# 07_MCU.net
KiCad netlist of a schematic drawn in Altium Designer
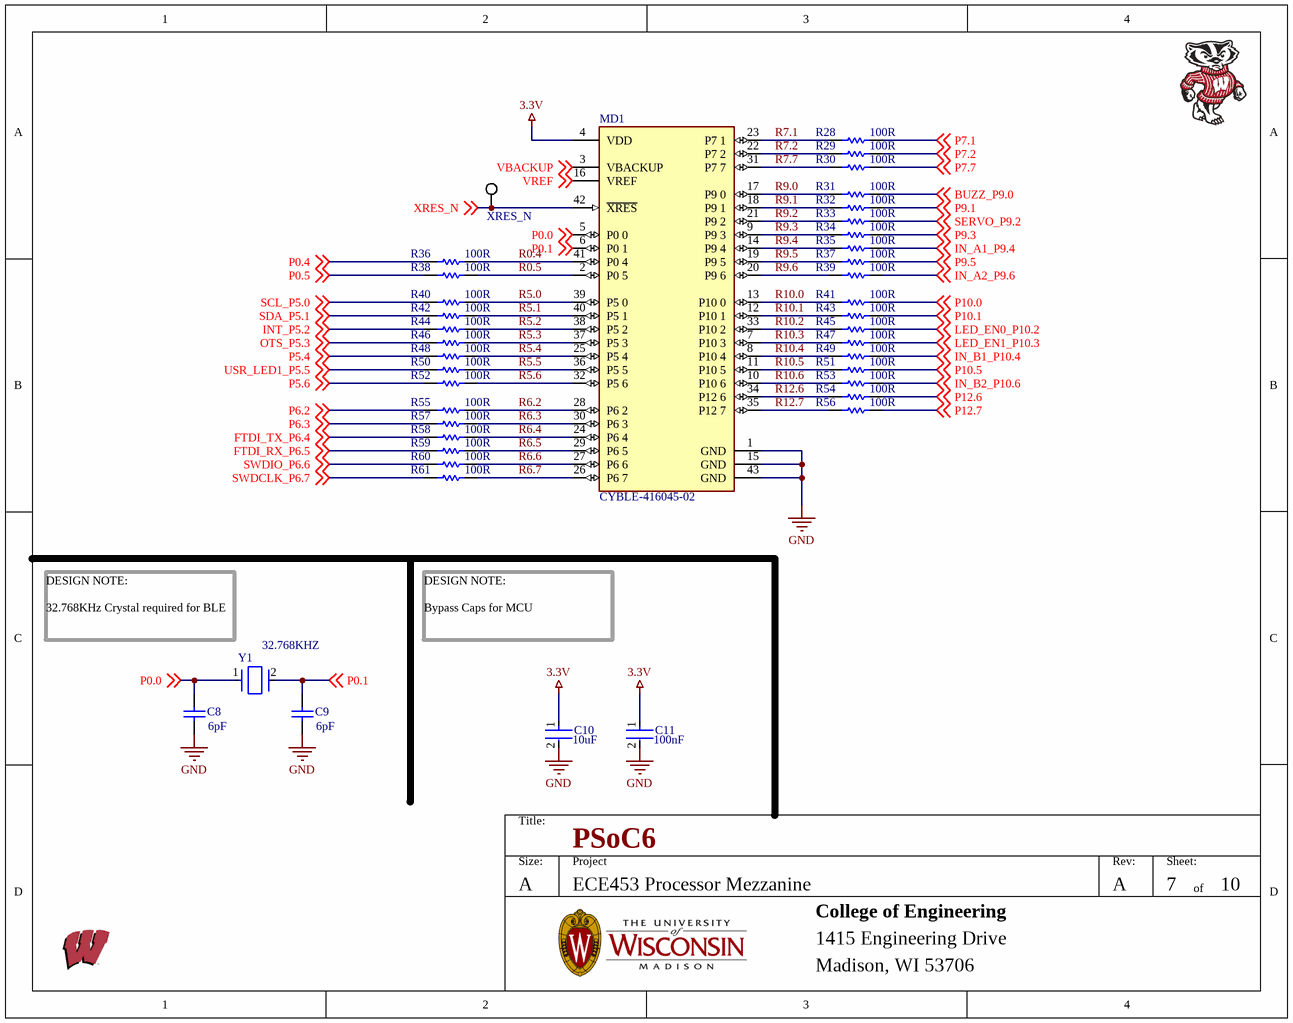
[diagram p0: 07_MCU.SchDoc]

(export (version "E")
  (design (tool "Eeschema 10.0.6"))
  (components
    (comp (ref "C8")
      (value "6pF")
      (footprint "CAPC2013X94X50LL20T25")
      (fields
        (field (name "MANUFACTURER") "KEMET")
        (field (name "MANUFACTURER PART NUMBER") "CBR08C609C5GAC")
        (field (name "Comment") "08055A6R0CAT2A")
      )
      (libsource (lib "Altium Content Vault") (part "CAP"))
    )
    (comp (ref "C9")
      (value "6pF")
      (footprint "CAPC2013X94X50LL20T25")
      (fields
        (field (name "MANUFACTURER") "KEMET")
        (field (name "MANUFACTURER PART NUMBER") "CBR08C609C5GAC")
        (field (name "Comment") "08055A6R0CAT2A")
      )
      (libsource (lib "Altium Content Vault") (part "CAP"))
    )
    (comp (ref "C10")
      (value "10uF")
      (footprint "FP-C0805C-DG-MFG")
      (description "CAP CER 10UF 10V X5R 0805")
      (fields
        (field (name "MANUFACTURER") "KEMET")
        (field (name "MANUFACTURER PART NUMBER") "C0805C106K8PACTU")
      )
      (libsource (lib "Altium Content Vault") (part "11868f565c42a9108669ba33697ecf6"))
    )
    (comp (ref "C11")
      (value "100nF")
      (footprint "FP-C0805C-DN-MFG")
      (description "CAP CER 0.1UF 50V X7R 0805")
      (fields
        (field (name "MANUFACTURER") "KEMET")
        (field (name "MANUFACTURER PART NUMBER") "C0805C104K5RACTU")
      )
      (libsource (lib "Altium Content Vault") (part "b4654b650e69147ec39a6b967a45e02"))
    )
    (comp (ref "MD1")
      (value "CYBLE-416045-02")
      (footprint "FP-CYBLE-416045-02-MFG")
      (description "RF TXRX MOD BLUETOOTH TRACE ANT")
      (fields
        (field (name "OCTOPART") "https://octopart.com/cyble-416045-02-cypress+semiconductor-96386825")
        (field (name "MANUFACTURER") "Cypress Semiconductor")
      )
      (libsource (lib "Altium Content Vault") (part "10a29a4e77099fbb6f911efb04878b1"))
    )
    (comp (ref "R28")
      (value "100R")
      (footprint "RESC2013X60X40ML20T25")
      (fields
        (field (name "MANUFACTURER") "Yageo")
        (field (name "MANUFACTURER PART NUMBER") "RC0805FR-07100RL")
        (field (name "TOLERANCE") "1%")
      )
      (libsource (lib "Altium Content Vault") (part "RES"))
    )
    (comp (ref "R29")
      (value "100R")
      (footprint "RESC2013X60X40ML20T25")
      (fields
        (field (name "MANUFACTURER") "Yageo")
        (field (name "MANUFACTURER PART NUMBER") "RC0805FR-07100RL")
        (field (name "TOLERANCE") "1%")
      )
      (libsource (lib "Altium Content Vault") (part "RES"))
    )
    (comp (ref "R30")
      (value "100R")
      (footprint "RESC2013X60X40ML20T25")
      (fields
        (field (name "MANUFACTURER") "Yageo")
        (field (name "MANUFACTURER PART NUMBER") "RC0805FR-07100RL")
        (field (name "TOLERANCE") "1%")
      )
      (libsource (lib "Altium Content Vault") (part "RES"))
    )
    (comp (ref "R31")
      (value "100R")
      (footprint "RESC2013X60X40ML20T25")
      (fields
        (field (name "MANUFACTURER") "Yageo")
        (field (name "MANUFACTURER PART NUMBER") "RC0805FR-07100RL")
        (field (name "TOLERANCE") "1%")
      )
      (libsource (lib "Altium Content Vault") (part "RES"))
    )
    (comp (ref "R32")
      (value "100R")
      (footprint "RESC2013X60X40ML20T25")
      (fields
        (field (name "MANUFACTURER") "Yageo")
        (field (name "MANUFACTURER PART NUMBER") "RC0805FR-07100RL")
        (field (name "TOLERANCE") "1%")
      )
      (libsource (lib "Altium Content Vault") (part "RES"))
    )
    (comp (ref "R33")
      (value "100R")
      (footprint "RESC2013X60X40ML20T25")
      (fields
        (field (name "MANUFACTURER") "Yageo")
        (field (name "MANUFACTURER PART NUMBER") "RC0805FR-07100RL")
        (field (name "TOLERANCE") "1%")
      )
      (libsource (lib "Altium Content Vault") (part "RES"))
    )
    (comp (ref "R34")
      (value "100R")
      (footprint "RESC2013X60X40ML20T25")
      (fields
        (field (name "MANUFACTURER") "Yageo")
        (field (name "MANUFACTURER PART NUMBER") "RC0805FR-07100RL")
        (field (name "TOLERANCE") "1%")
      )
      (libsource (lib "Altium Content Vault") (part "RES"))
    )
    (comp (ref "R35")
      (value "100R")
      (footprint "RESC2013X60X40ML20T25")
      (fields
        (field (name "MANUFACTURER") "Yageo")
        (field (name "MANUFACTURER PART NUMBER") "RC0805FR-07100RL")
        (field (name "TOLERANCE") "1%")
      )
      (libsource (lib "Altium Content Vault") (part "RES"))
    )
    (comp (ref "R36")
      (value "100R")
      (footprint "RESC2013X60X40ML20T25")
      (fields
        (field (name "MANUFACTURER") "Yageo")
        (field (name "MANUFACTURER PART NUMBER") "RC0805FR-07100RL")
        (field (name "TOLERANCE") "1%")
      )
      (libsource (lib "Altium Content Vault") (part "RES"))
    )
    (comp (ref "R37")
      (value "100R")
      (footprint "RESC2013X60X40ML20T25")
      (fields
        (field (name "MANUFACTURER") "Yageo")
        (field (name "MANUFACTURER PART NUMBER") "RC0805FR-07100RL")
        (field (name "TOLERANCE") "1%")
      )
      (libsource (lib "Altium Content Vault") (part "RES"))
    )
    (comp (ref "R38")
      (value "100R")
      (footprint "RESC2013X60X40ML20T25")
      (fields
        (field (name "MANUFACTURER") "Yageo")
        (field (name "MANUFACTURER PART NUMBER") "RC0805FR-07100RL")
        (field (name "TOLERANCE") "1%")
      )
      (libsource (lib "Altium Content Vault") (part "RES"))
    )
    (comp (ref "R39")
      (value "100R")
      (footprint "RESC2013X60X40ML20T25")
      (fields
        (field (name "MANUFACTURER") "Yageo")
        (field (name "MANUFACTURER PART NUMBER") "RC0805FR-07100RL")
        (field (name "TOLERANCE") "1%")
      )
      (libsource (lib "Altium Content Vault") (part "RES"))
    )
    (comp (ref "R40")
      (value "100R")
      (footprint "RESC2013X60X40ML20T25")
      (fields
        (field (name "MANUFACTURER") "Yageo")
        (field (name "MANUFACTURER PART NUMBER") "RC0805FR-07100RL")
        (field (name "TOLERANCE") "1%")
      )
      (libsource (lib "Altium Content Vault") (part "RES"))
    )
    (comp (ref "R41")
      (value "100R")
      (footprint "RESC2013X60X40ML20T25")
      (fields
        (field (name "MANUFACTURER") "Yageo")
        (field (name "MANUFACTURER PART NUMBER") "RC0805FR-07100RL")
        (field (name "TOLERANCE") "1%")
      )
      (libsource (lib "Altium Content Vault") (part "RES"))
    )
    (comp (ref "R42")
      (value "100R")
      (footprint "RESC2013X60X40ML20T25")
      (fields
        (field (name "MANUFACTURER") "Yageo")
        (field (name "MANUFACTURER PART NUMBER") "RC0805FR-07100RL")
        (field (name "TOLERANCE") "1%")
      )
      (libsource (lib "Altium Content Vault") (part "RES"))
    )
    (comp (ref "R43")
      (value "100R")
      (footprint "RESC2013X60X40ML20T25")
      (fields
        (field (name "MANUFACTURER") "Yageo")
        (field (name "MANUFACTURER PART NUMBER") "RC0805FR-07100RL")
        (field (name "TOLERANCE") "1%")
      )
      (libsource (lib "Altium Content Vault") (part "RES"))
    )
    (comp (ref "R44")
      (value "100R")
      (footprint "RESC2013X60X40ML20T25")
      (fields
        (field (name "MANUFACTURER") "Yageo")
        (field (name "MANUFACTURER PART NUMBER") "RC0805FR-07100RL")
        (field (name "TOLERANCE") "1%")
      )
      (libsource (lib "Altium Content Vault") (part "RES"))
    )
    (comp (ref "R45")
      (value "100R")
      (footprint "RESC2013X60X40ML20T25")
      (fields
        (field (name "MANUFACTURER") "Yageo")
        (field (name "MANUFACTURER PART NUMBER") "RC0805FR-07100RL")
        (field (name "TOLERANCE") "1%")
      )
      (libsource (lib "Altium Content Vault") (part "RES"))
    )
    (comp (ref "R46")
      (value "100R")
      (footprint "RESC2013X60X40ML20T25")
      (fields
        (field (name "MANUFACTURER") "Yageo")
        (field (name "MANUFACTURER PART NUMBER") "RC0805FR-07100RL")
        (field (name "TOLERANCE") "1%")
      )
      (libsource (lib "Altium Content Vault") (part "RES"))
    )
    (comp (ref "R47")
      (value "100R")
      (footprint "RESC2013X60X40ML20T25")
      (fields
        (field (name "MANUFACTURER") "Yageo")
        (field (name "MANUFACTURER PART NUMBER") "RC0805FR-07100RL")
        (field (name "TOLERANCE") "1%")
      )
      (libsource (lib "Altium Content Vault") (part "RES"))
    )
    (comp (ref "R48")
      (value "100R")
      (footprint "RESC2013X60X40ML20T25")
      (fields
        (field (name "MANUFACTURER") "Yageo")
        (field (name "MANUFACTURER PART NUMBER") "RC0805FR-07100RL")
        (field (name "TOLERANCE") "1%")
      )
      (libsource (lib "Altium Content Vault") (part "RES"))
    )
    (comp (ref "R49")
      (value "100R")
      (footprint "RESC2013X60X40ML20T25")
      (fields
        (field (name "MANUFACTURER") "Yageo")
        (field (name "MANUFACTURER PART NUMBER") "RC0805FR-07100RL")
        (field (name "TOLERANCE") "1%")
      )
      (libsource (lib "Altium Content Vault") (part "RES"))
    )
    (comp (ref "R50")
      (value "100R")
      (footprint "RESC2013X60X40ML20T25")
      (fields
        (field (name "MANUFACTURER") "Yageo")
        (field (name "MANUFACTURER PART NUMBER") "RC0805FR-07100RL")
        (field (name "TOLERANCE") "1%")
      )
      (libsource (lib "Altium Content Vault") (part "RES"))
    )
    (comp (ref "R51")
      (value "100R")
      (footprint "RESC2013X60X40ML20T25")
      (fields
        (field (name "MANUFACTURER") "Yageo")
        (field (name "MANUFACTURER PART NUMBER") "RC0805FR-07100RL")
        (field (name "TOLERANCE") "1%")
      )
      (libsource (lib "Altium Content Vault") (part "RES"))
    )
    (comp (ref "R52")
      (value "100R")
      (footprint "RESC2013X60X40ML20T25")
      (fields
        (field (name "MANUFACTURER") "Yageo")
        (field (name "MANUFACTURER PART NUMBER") "RC0805FR-07100RL")
        (field (name "TOLERANCE") "1%")
      )
      (libsource (lib "Altium Content Vault") (part "RES"))
    )
    (comp (ref "R53")
      (value "100R")
      (footprint "RESC2013X60X40ML20T25")
      (fields
        (field (name "MANUFACTURER") "Yageo")
        (field (name "MANUFACTURER PART NUMBER") "RC0805FR-07100RL")
        (field (name "TOLERANCE") "1%")
      )
      (libsource (lib "Altium Content Vault") (part "RES"))
    )
    (comp (ref "R54")
      (value "100R")
      (footprint "RESC2013X60X40ML20T25")
      (fields
        (field (name "MANUFACTURER") "Yageo")
        (field (name "MANUFACTURER PART NUMBER") "RC0805FR-07100RL")
        (field (name "TOLERANCE") "1%")
      )
      (libsource (lib "Altium Content Vault") (part "RES"))
    )
    (comp (ref "R55")
      (value "100R")
      (footprint "RESC2013X60X40ML20T25")
      (fields
        (field (name "MANUFACTURER") "Yageo")
        (field (name "MANUFACTURER PART NUMBER") "RC0805FR-07100RL")
        (field (name "TOLERANCE") "1%")
      )
      (libsource (lib "Altium Content Vault") (part "RES"))
    )
    (comp (ref "R56")
      (value "100R")
      (footprint "RESC2013X60X40ML20T25")
      (fields
        (field (name "MANUFACTURER") "Yageo")
        (field (name "MANUFACTURER PART NUMBER") "RC0805FR-07100RL")
        (field (name "TOLERANCE") "1%")
      )
      (libsource (lib "Altium Content Vault") (part "RES"))
    )
    (comp (ref "R57")
      (value "100R")
      (footprint "RESC2013X60X40ML20T25")
      (fields
        (field (name "MANUFACTURER") "Yageo")
        (field (name "MANUFACTURER PART NUMBER") "RC0805FR-07100RL")
        (field (name "TOLERANCE") "1%")
      )
      (libsource (lib "Altium Content Vault") (part "RES"))
    )
    (comp (ref "R58")
      (value "100R")
      (footprint "RESC2013X60X40ML20T25")
      (fields
        (field (name "MANUFACTURER") "Yageo")
        (field (name "MANUFACTURER PART NUMBER") "RC0805FR-07100RL")
        (field (name "TOLERANCE") "1%")
      )
      (libsource (lib "Altium Content Vault") (part "RES"))
    )
    (comp (ref "R59")
      (value "100R")
      (footprint "RESC2013X60X40ML20T25")
      (fields
        (field (name "MANUFACTURER") "Yageo")
        (field (name "MANUFACTURER PART NUMBER") "RC0805FR-07100RL")
        (field (name "TOLERANCE") "1%")
      )
      (libsource (lib "Altium Content Vault") (part "RES"))
    )
    (comp (ref "R60")
      (value "100R")
      (footprint "RESC2013X60X40ML20T25")
      (fields
        (field (name "MANUFACTURER") "Yageo")
        (field (name "MANUFACTURER PART NUMBER") "RC0805FR-07100RL")
        (field (name "TOLERANCE") "1%")
      )
      (libsource (lib "Altium Content Vault") (part "RES"))
    )
    (comp (ref "R61")
      (value "100R")
      (footprint "RESC2013X60X40ML20T25")
      (fields
        (field (name "MANUFACTURER") "Yageo")
        (field (name "MANUFACTURER PART NUMBER") "RC0805FR-07100RL")
        (field (name "TOLERANCE") "1%")
      )
      (libsource (lib "Altium Content Vault") (part "RES"))
    )
    (comp (ref "XRES_N")
      (value "5019")
      (footprint "KSTN-5019_V")
      (description "Test Point, 1 Position SMD, RoHS, Tape and Reel")
      (fields (field (name "MANUFACTURER") "Keystone Electronics"))
      (libsource (lib "Altium Content Vault") (part "TESTPOINT_WHITE"))
    )
    (comp (ref "Y1")
      (value "32.768KHZ")
      (footprint "FP-ABS07-120-MFG")
      (description "CRYSTAL 32.7680KHZ 6PF SMD")
      (fields
        (field (name "MANUFACTURER") "Abracon")
        (field (name "MANUFACTURER PART NUMBER") "ABS07-120-32.768KHZ-T")
      )
      (libsource (lib "Altium Content Vault") (part "c23a69dc6c9e2f18f2079038eb95dd1"))
    )
  )
  (nets
    (net (code "1") (name "/R0.4") (class "Default")
      (node (ref "MD1") (pin "41") (pinfunction "P0_4_41") (pintype "bidirectional"))
      (node (ref "R36") (pin "2") (pinfunction "2_2") (pintype "passive"))
    )
    (net (code "2") (name "/R0.5") (class "Default")
      (node (ref "MD1") (pin "2") (pinfunction "P0_5_2") (pintype "bidirectional"))
      (node (ref "R38") (pin "2") (pinfunction "2_2") (pintype "passive"))
    )
    (net (code "3") (name "/R5.0") (class "Default")
      (node (ref "MD1") (pin "39") (pinfunction "P5_0_39") (pintype "bidirectional"))
      (node (ref "R40") (pin "2") (pinfunction "2_2") (pintype "passive"))
    )
    (net (code "4") (name "/R5.1") (class "Default")
      (node (ref "MD1") (pin "40") (pinfunction "P5_1_40") (pintype "bidirectional"))
      (node (ref "R42") (pin "2") (pinfunction "2_2") (pintype "passive"))
    )
    (net (code "5") (name "/R5.2") (class "Default")
      (node (ref "MD1") (pin "38") (pinfunction "P5_2_38") (pintype "bidirectional"))
      (node (ref "R44") (pin "2") (pinfunction "2_2") (pintype "passive"))
    )
    (net (code "6") (name "/R5.3") (class "Default")
      (node (ref "MD1") (pin "37") (pinfunction "P5_3_37") (pintype "bidirectional"))
      (node (ref "R46") (pin "2") (pinfunction "2_2") (pintype "passive"))
    )
    (net (code "7") (name "/R5.4") (class "Default")
      (node (ref "MD1") (pin "25") (pinfunction "P5_4_25") (pintype "bidirectional"))
      (node (ref "R48") (pin "2") (pinfunction "2_2") (pintype "passive"))
    )
    (net (code "8") (name "/R5.5") (class "Default")
      (node (ref "MD1") (pin "36") (pinfunction "P5_5_36") (pintype "bidirectional"))
      (node (ref "R50") (pin "2") (pinfunction "2_2") (pintype "passive"))
    )
    (net (code "9") (name "/R5.6") (class "Default")
      (node (ref "MD1") (pin "32") (pinfunction "P5_6_32") (pintype "bidirectional"))
      (node (ref "R52") (pin "2") (pinfunction "2_2") (pintype "passive"))
    )
    (net (code "10") (name "/R6.2") (class "Default")
      (node (ref "MD1") (pin "28") (pinfunction "P6_2_28") (pintype "bidirectional"))
      (node (ref "R55") (pin "2") (pinfunction "2_2") (pintype "passive"))
    )
    (net (code "11") (name "/R6.3") (class "Default")
      (node (ref "MD1") (pin "30") (pinfunction "P6_3_30") (pintype "bidirectional"))
      (node (ref "R57") (pin "2") (pinfunction "2_2") (pintype "passive"))
    )
    (net (code "12") (name "/R6.4") (class "Default")
      (node (ref "MD1") (pin "24") (pinfunction "P6_4_24") (pintype "bidirectional"))
      (node (ref "R58") (pin "2") (pinfunction "2_2") (pintype "passive"))
    )
    (net (code "13") (name "/R6.5") (class "Default")
      (node (ref "MD1") (pin "29") (pinfunction "P6_5_29") (pintype "bidirectional"))
      (node (ref "R59") (pin "2") (pinfunction "2_2") (pintype "passive"))
    )
    (net (code "14") (name "/R6.6") (class "Default")
      (node (ref "MD1") (pin "27") (pinfunction "P6_6_27") (pintype "bidirectional"))
      (node (ref "R60") (pin "2") (pinfunction "2_2") (pintype "passive"))
    )
    (net (code "15") (name "/R6.7") (class "Default")
      (node (ref "MD1") (pin "26") (pinfunction "P6_7_26") (pintype "bidirectional"))
      (node (ref "R61") (pin "2") (pinfunction "2_2") (pintype "passive"))
    )
    (net (code "16") (name "/R7.1") (class "Default")
      (node (ref "MD1") (pin "23") (pinfunction "P7_1_23") (pintype "bidirectional"))
      (node (ref "R28") (pin "1") (pinfunction "1_1") (pintype "passive"))
    )
    (net (code "17") (name "/R7.2") (class "Default")
      (node (ref "MD1") (pin "22") (pinfunction "P7_2_22") (pintype "bidirectional"))
      (node (ref "R29") (pin "1") (pinfunction "1_1") (pintype "passive"))
    )
    (net (code "18") (name "/R7.7") (class "Default")
      (node (ref "MD1") (pin "31") (pinfunction "P7_7_31") (pintype "bidirectional"))
      (node (ref "R30") (pin "1") (pinfunction "1_1") (pintype "passive"))
    )
    (net (code "19") (name "/R9.0") (class "Default")
      (node (ref "MD1") (pin "17") (pinfunction "P9_0_17") (pintype "bidirectional"))
      (node (ref "R31") (pin "1") (pinfunction "1_1") (pintype "passive"))
    )
    (net (code "20") (name "/R9.1") (class "Default")
      (node (ref "MD1") (pin "18") (pinfunction "P9_1_18") (pintype "bidirectional"))
      (node (ref "R32") (pin "1") (pinfunction "1_1") (pintype "passive"))
    )
    (net (code "21") (name "/R9.2") (class "Default")
      (node (ref "MD1") (pin "21") (pinfunction "P9_2_21") (pintype "bidirectional"))
      (node (ref "R33") (pin "1") (pinfunction "1_1") (pintype "passive"))
    )
    (net (code "22") (name "/R9.3") (class "Default")
      (node (ref "MD1") (pin "9") (pinfunction "P9_3_9") (pintype "bidirectional"))
      (node (ref "R34") (pin "1") (pinfunction "1_1") (pintype "passive"))
    )
    (net (code "23") (name "/R9.4") (class "Default")
      (node (ref "MD1") (pin "14") (pinfunction "P9_4_14") (pintype "bidirectional"))
      (node (ref "R35") (pin "1") (pinfunction "1_1") (pintype "passive"))
    )
    (net (code "24") (name "/R9.5") (class "Default")
      (node (ref "MD1") (pin "19") (pinfunction "P9_5_19") (pintype "bidirectional"))
      (node (ref "R37") (pin "1") (pinfunction "1_1") (pintype "passive"))
    )
    (net (code "25") (name "/R9.6") (class "Default")
      (node (ref "MD1") (pin "20") (pinfunction "P9_6_20") (pintype "bidirectional"))
      (node (ref "R39") (pin "1") (pinfunction "1_1") (pintype "passive"))
    )
    (net (code "26") (name "/R10.0") (class "Default")
      (node (ref "MD1") (pin "13") (pinfunction "P10_0_13") (pintype "bidirectional"))
      (node (ref "R41") (pin "1") (pinfunction "1_1") (pintype "passive"))
    )
    (net (code "27") (name "/R10.1") (class "Default")
      (node (ref "MD1") (pin "12") (pinfunction "P10_1_12") (pintype "bidirectional"))
      (node (ref "R43") (pin "1") (pinfunction "1_1") (pintype "passive"))
    )
    (net (code "28") (name "/R10.2") (class "Default")
      (node (ref "MD1") (pin "33") (pinfunction "P10_2_33") (pintype "bidirectional"))
      (node (ref "R45") (pin "1") (pinfunction "1_1") (pintype "passive"))
    )
    (net (code "29") (name "/R10.3") (class "Default")
      (node (ref "MD1") (pin "7") (pinfunction "P10_3_7") (pintype "bidirectional"))
      (node (ref "R47") (pin "1") (pinfunction "1_1") (pintype "passive"))
    )
    (net (code "30") (name "/R10.4") (class "Default")
      (node (ref "MD1") (pin "8") (pinfunction "P10_4_8") (pintype "bidirectional"))
      (node (ref "R49") (pin "1") (pinfunction "1_1") (pintype "passive"))
    )
    (net (code "31") (name "/R10.5") (class "Default")
      (node (ref "MD1") (pin "11") (pinfunction "P10_5_11") (pintype "bidirectional"))
      (node (ref "R51") (pin "1") (pinfunction "1_1") (pintype "passive"))
    )
    (net (code "32") (name "/R10.6") (class "Default")
      (node (ref "MD1") (pin "10") (pinfunction "P10_6_10") (pintype "bidirectional"))
      (node (ref "R53") (pin "1") (pinfunction "1_1") (pintype "passive"))
    )
    (net (code "33") (name "/R12.6") (class "Default")
      (node (ref "MD1") (pin "34") (pinfunction "P12_6_34") (pintype "bidirectional"))
      (node (ref "R54") (pin "1") (pinfunction "1_1") (pintype "passive"))
    )
    (net (code "34") (name "/R12.7") (class "Default")
      (node (ref "MD1") (pin "35") (pinfunction "P12_7_35") (pintype "bidirectional"))
      (node (ref "R56") (pin "1") (pinfunction "1_1") (pintype "passive"))
    )
    (net (code "35") (name "3.3V") (class "Default")
      (node (ref "C10") (pin "1") (pinfunction "1_1") (pintype "passive"))
      (node (ref "C11") (pin "1") (pinfunction "1_1") (pintype "passive"))
      (node (ref "MD1") (pin "4") (pinfunction "VDD_4") (pintype "power_in"))
    )
    (net (code "36") (name "BUZZ_P9.0") (class "Default")
      (node (ref "R31") (pin "2") (pinfunction "2_2") (pintype "passive"))
    )
    (net (code "37") (name "FTDI_RX_P6.5") (class "Default")
      (node (ref "R59") (pin "1") (pinfunction "1_1") (pintype "passive"))
    )
    (net (code "38") (name "FTDI_TX_P6.4") (class "Default")
      (node (ref "R58") (pin "1") (pinfunction "1_1") (pintype "passive"))
    )
    (net (code "39") (name "GND") (class "Default")
      (node (ref "C10") (pin "2") (pinfunction "2_2") (pintype "passive"))
      (node (ref "C11") (pin "2") (pinfunction "2_2") (pintype "passive"))
      (node (ref "C8") (pin "1") (pinfunction "1_1") (pintype "passive"))
      (node (ref "C9") (pin "1") (pinfunction "1_1") (pintype "passive"))
      (node (ref "MD1") (pin "1") (pinfunction "GND_1") (pintype "power_in"))
      (node (ref "MD1") (pin "15") (pinfunction "GND_15") (pintype "power_in"))
      (node (ref "MD1") (pin "43") (pinfunction "GND_43") (pintype "power_in"))
    )
    (net (code "40") (name "INT_P5.2") (class "Default")
      (node (ref "R44") (pin "1") (pinfunction "1_1") (pintype "passive"))
    )
    (net (code "41") (name "IN_A1_P9.4") (class "Default")
      (node (ref "R35") (pin "2") (pinfunction "2_2") (pintype "passive"))
    )
    (net (code "42") (name "IN_A2_P9.6") (class "Default")
      (node (ref "R39") (pin "2") (pinfunction "2_2") (pintype "passive"))
    )
    (net (code "43") (name "IN_B1_P10.4") (class "Default")
      (node (ref "R49") (pin "2") (pinfunction "2_2") (pintype "passive"))
    )
    (net (code "44") (name "IN_B2_P10.6") (class "Default")
      (node (ref "R53") (pin "2") (pinfunction "2_2") (pintype "passive"))
    )
    (net (code "45") (name "LED_EN0_P10.2") (class "Default")
      (node (ref "R45") (pin "2") (pinfunction "2_2") (pintype "passive"))
    )
    (net (code "46") (name "LED_EN1_P10.3") (class "Default")
      (node (ref "R47") (pin "2") (pinfunction "2_2") (pintype "passive"))
    )
    (net (code "47") (name "OTS_P5.3") (class "Default")
      (node (ref "R46") (pin "1") (pinfunction "1_1") (pintype "passive"))
    )
    (net (code "48") (name "P0.0") (class "Default")
      (node (ref "C8") (pin "2") (pinfunction "2_2") (pintype "passive"))
      (node (ref "MD1") (pin "5") (pinfunction "P0_0_5") (pintype "bidirectional"))
      (node (ref "Y1") (pin "1") (pinfunction "1_1") (pintype "passive"))
    )
    (net (code "49") (name "P0.1") (class "Default")
      (node (ref "C9") (pin "2") (pinfunction "2_2") (pintype "passive"))
      (node (ref "MD1") (pin "6") (pinfunction "P0_1_6") (pintype "bidirectional"))
      (node (ref "Y1") (pin "2") (pinfunction "2_2") (pintype "passive"))
    )
    (net (code "50") (name "P0.4") (class "Default")
      (node (ref "R36") (pin "1") (pinfunction "1_1") (pintype "passive"))
    )
    (net (code "51") (name "P0.5") (class "Default")
      (node (ref "R38") (pin "1") (pinfunction "1_1") (pintype "passive"))
    )
    (net (code "52") (name "P5.4") (class "Default")
      (node (ref "R48") (pin "1") (pinfunction "1_1") (pintype "passive"))
    )
    (net (code "53") (name "P5.6") (class "Default")
      (node (ref "R52") (pin "1") (pinfunction "1_1") (pintype "passive"))
    )
    (net (code "54") (name "P6.2") (class "Default")
      (node (ref "R55") (pin "1") (pinfunction "1_1") (pintype "passive"))
    )
    (net (code "55") (name "P6.3") (class "Default")
      (node (ref "R57") (pin "1") (pinfunction "1_1") (pintype "passive"))
    )
    (net (code "56") (name "P7.1") (class "Default")
      (node (ref "R28") (pin "2") (pinfunction "2_2") (pintype "passive"))
    )
    (net (code "57") (name "P7.2") (class "Default")
      (node (ref "R29") (pin "2") (pinfunction "2_2") (pintype "passive"))
    )
    (net (code "58") (name "P7.7") (class "Default")
      (node (ref "R30") (pin "2") (pinfunction "2_2") (pintype "passive"))
    )
    (net (code "59") (name "P9.1") (class "Default")
      (node (ref "R32") (pin "2") (pinfunction "2_2") (pintype "passive"))
    )
    (net (code "60") (name "P9.3") (class "Default")
      (node (ref "R34") (pin "2") (pinfunction "2_2") (pintype "passive"))
    )
    (net (code "61") (name "P9.5") (class "Default")
      (node (ref "R37") (pin "2") (pinfunction "2_2") (pintype "passive"))
    )
    (net (code "62") (name "P10.0") (class "Default")
      (node (ref "R41") (pin "2") (pinfunction "2_2") (pintype "passive"))
    )
    (net (code "63") (name "P10.1") (class "Default")
      (node (ref "R43") (pin "2") (pinfunction "2_2") (pintype "passive"))
    )
    (net (code "64") (name "P10.5") (class "Default")
      (node (ref "R51") (pin "2") (pinfunction "2_2") (pintype "passive"))
    )
    (net (code "65") (name "P12.6") (class "Default")
      (node (ref "R54") (pin "2") (pinfunction "2_2") (pintype "passive"))
    )
    (net (code "66") (name "P12.7") (class "Default")
      (node (ref "R56") (pin "2") (pinfunction "2_2") (pintype "passive"))
    )
    (net (code "67") (name "SCL_P5.0") (class "Default")
      (node (ref "R40") (pin "1") (pinfunction "1_1") (pintype "passive"))
    )
    (net (code "68") (name "SDA_P5.1") (class "Default")
      (node (ref "R42") (pin "1") (pinfunction "1_1") (pintype "passive"))
    )
    (net (code "69") (name "SERVO_P9.2") (class "Default")
      (node (ref "R33") (pin "2") (pinfunction "2_2") (pintype "passive"))
    )
    (net (code "70") (name "SWDCLK_P6.7") (class "Default")
      (node (ref "R61") (pin "1") (pinfunction "1_1") (pintype "passive"))
    )
    (net (code "71") (name "SWDIO_P6.6") (class "Default")
      (node (ref "R60") (pin "1") (pinfunction "1_1") (pintype "passive"))
    )
    (net (code "72") (name "USR_LED1_P5.5") (class "Default")
      (node (ref "R50") (pin "1") (pinfunction "1_1") (pintype "passive"))
    )
    (net (code "73") (name "VBACKUP") (class "Default")
      (node (ref "MD1") (pin "3") (pinfunction "VBACKUP_3") (pintype "power_in"))
    )
    (net (code "74") (name "VREF") (class "Default")
      (node (ref "MD1") (pin "16") (pinfunction "VREF_16") (pintype "power_in"))
    )
    (net (code "75") (name "XRES_N") (class "Default")
      (node (ref "MD1") (pin "42") (pinfunction "~{XRES}_42") (pintype "input"))
      (node (ref "XRES_N") (pin "1") (pinfunction "1_1") (pintype "passive"))
    )
  )
)
